# MainRTD.net
KiCad netlist of a schematic drawn in Altium Designer
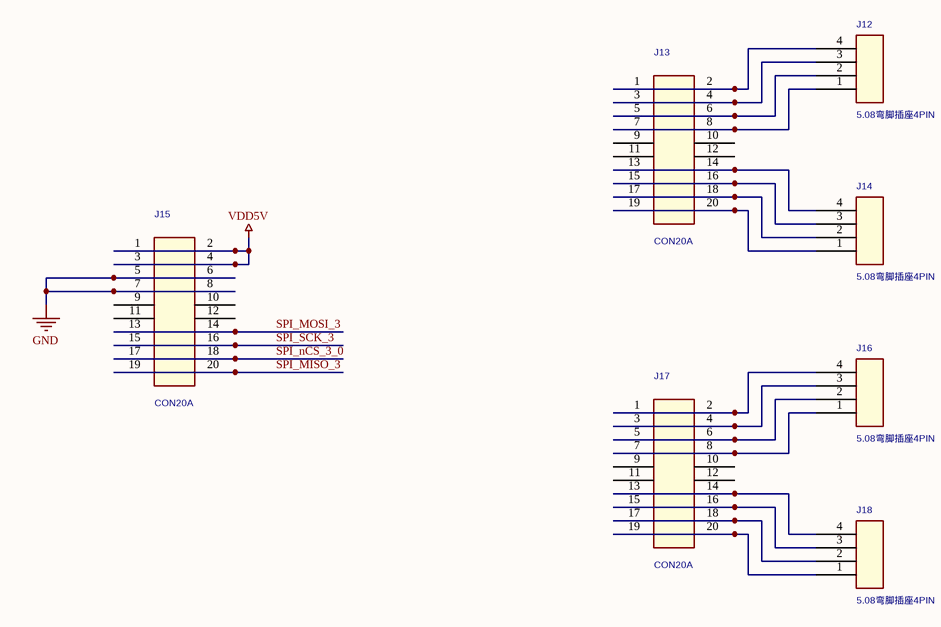
[diagram p0: MainRTD.SchDoc]

(export (version "E")
  (design (tool "Eeschema 10.0.6"))
  (components
    (comp (ref "J12") (value "5.08弯脚插座4PIN") (footprint "JIEKE_4PX508") (libsource (lib "*") (part "CON4")))
    (comp (ref "J13") (value "CON20A") (footprint "HDR2X10") (libsource (lib "*") (part "CON20A")))
    (comp (ref "J14") (value "5.08弯脚插座4PIN") (footprint "JIEKE_4PX508") (libsource (lib "*") (part "CON4")))
    (comp (ref "J15") (value "CON20A") (footprint "HDR2X10") (libsource (lib "*") (part "CON20A")))
    (comp (ref "J16") (value "5.08弯脚插座4PIN") (footprint "JIEKE_4PX508") (libsource (lib "*") (part "CON4")))
    (comp (ref "J17") (value "CON20A") (footprint "HDR2X10") (libsource (lib "*") (part "CON20A")))
    (comp (ref "J18") (value "5.08弯脚插座4PIN") (footprint "JIEKE_4PX508") (libsource (lib "*") (part "CON4")))
  )
  (nets
    (net (code "1") (name "/SPI_MISO_3") (class "Default")
      (node (ref "J15") (pin "19") (pinfunction "19_19") (pintype "passive"))
      (node (ref "J15") (pin "20") (pinfunction "20_20") (pintype "passive"))
    )
    (net (code "2") (name "/SPI_MOSI_3") (class "Default")
      (node (ref "J15") (pin "13") (pinfunction "13_13") (pintype "passive"))
      (node (ref "J15") (pin "14") (pinfunction "14_14") (pintype "passive"))
    )
    (net (code "3") (name "/SPI_SCK_3") (class "Default")
      (node (ref "J15") (pin "15") (pinfunction "15_15") (pintype "passive"))
      (node (ref "J15") (pin "16") (pinfunction "16_16") (pintype "passive"))
    )
    (net (code "4") (name "/SPI_nCS_3_0") (class "Default")
      (node (ref "J15") (pin "17") (pinfunction "17_17") (pintype "passive"))
      (node (ref "J15") (pin "18") (pinfunction "18_18") (pintype "passive"))
    )
    (net (code "5") (name "GND") (class "Default")
      (node (ref "J15") (pin "5") (pinfunction "5_5") (pintype "passive"))
      (node (ref "J15") (pin "6") (pinfunction "6_6") (pintype "passive"))
      (node (ref "J15") (pin "7") (pinfunction "7_7") (pintype "passive"))
      (node (ref "J15") (pin "8") (pinfunction "8_8") (pintype "passive"))
    )
    (net (code "6") (name "Net-(J12-Pad1)") (class "Default")
      (node (ref "J12") (pin "1") (pinfunction "1_1") (pintype "passive"))
      (node (ref "J13") (pin "7") (pinfunction "7_7") (pintype "passive"))
      (node (ref "J13") (pin "8") (pinfunction "8_8") (pintype "passive"))
    )
    (net (code "7") (name "Net-(J12-Pad2)") (class "Default")
      (node (ref "J12") (pin "2") (pinfunction "2_2") (pintype "passive"))
      (node (ref "J13") (pin "5") (pinfunction "5_5") (pintype "passive"))
      (node (ref "J13") (pin "6") (pinfunction "6_6") (pintype "passive"))
    )
    (net (code "8") (name "Net-(J12-Pad3)") (class "Default")
      (node (ref "J12") (pin "3") (pinfunction "3_3") (pintype "passive"))
      (node (ref "J13") (pin "3") (pinfunction "3_3") (pintype "passive"))
      (node (ref "J13") (pin "4") (pinfunction "4_4") (pintype "passive"))
    )
    (net (code "9") (name "Net-(J12-Pad4)") (class "Default")
      (node (ref "J12") (pin "4") (pinfunction "4_4") (pintype "passive"))
      (node (ref "J13") (pin "1") (pinfunction "1_1") (pintype "passive"))
      (node (ref "J13") (pin "2") (pinfunction "2_2") (pintype "passive"))
    )
    (net (code "10") (name "Net-(J13-Pad13)") (class "Default")
      (node (ref "J13") (pin "13") (pinfunction "13_13") (pintype "passive"))
      (node (ref "J13") (pin "14") (pinfunction "14_14") (pintype "passive"))
      (node (ref "J14") (pin "4") (pinfunction "4_4") (pintype "passive"))
    )
    (net (code "11") (name "Net-(J13-Pad15)") (class "Default")
      (node (ref "J13") (pin "15") (pinfunction "15_15") (pintype "passive"))
      (node (ref "J13") (pin "16") (pinfunction "16_16") (pintype "passive"))
      (node (ref "J14") (pin "3") (pinfunction "3_3") (pintype "passive"))
    )
    (net (code "12") (name "Net-(J13-Pad17)") (class "Default")
      (node (ref "J13") (pin "17") (pinfunction "17_17") (pintype "passive"))
      (node (ref "J13") (pin "18") (pinfunction "18_18") (pintype "passive"))
      (node (ref "J14") (pin "2") (pinfunction "2_2") (pintype "passive"))
    )
    (net (code "13") (name "Net-(J13-Pad19)") (class "Default")
      (node (ref "J13") (pin "19") (pinfunction "19_19") (pintype "passive"))
      (node (ref "J13") (pin "20") (pinfunction "20_20") (pintype "passive"))
      (node (ref "J14") (pin "1") (pinfunction "1_1") (pintype "passive"))
    )
    (net (code "14") (name "Net-(J16-Pad1)") (class "Default")
      (node (ref "J16") (pin "1") (pinfunction "1_1") (pintype "passive"))
      (node (ref "J17") (pin "7") (pinfunction "7_7") (pintype "passive"))
      (node (ref "J17") (pin "8") (pinfunction "8_8") (pintype "passive"))
    )
    (net (code "15") (name "Net-(J16-Pad2)") (class "Default")
      (node (ref "J16") (pin "2") (pinfunction "2_2") (pintype "passive"))
      (node (ref "J17") (pin "5") (pinfunction "5_5") (pintype "passive"))
      (node (ref "J17") (pin "6") (pinfunction "6_6") (pintype "passive"))
    )
    (net (code "16") (name "Net-(J16-Pad3)") (class "Default")
      (node (ref "J16") (pin "3") (pinfunction "3_3") (pintype "passive"))
      (node (ref "J17") (pin "3") (pinfunction "3_3") (pintype "passive"))
      (node (ref "J17") (pin "4") (pinfunction "4_4") (pintype "passive"))
    )
    (net (code "17") (name "Net-(J16-Pad4)") (class "Default")
      (node (ref "J16") (pin "4") (pinfunction "4_4") (pintype "passive"))
      (node (ref "J17") (pin "1") (pinfunction "1_1") (pintype "passive"))
      (node (ref "J17") (pin "2") (pinfunction "2_2") (pintype "passive"))
    )
    (net (code "18") (name "Net-(J17-Pad13)") (class "Default")
      (node (ref "J17") (pin "13") (pinfunction "13_13") (pintype "passive"))
      (node (ref "J17") (pin "14") (pinfunction "14_14") (pintype "passive"))
      (node (ref "J18") (pin "4") (pinfunction "4_4") (pintype "passive"))
    )
    (net (code "19") (name "Net-(J17-Pad15)") (class "Default")
      (node (ref "J17") (pin "15") (pinfunction "15_15") (pintype "passive"))
      (node (ref "J17") (pin "16") (pinfunction "16_16") (pintype "passive"))
      (node (ref "J18") (pin "3") (pinfunction "3_3") (pintype "passive"))
    )
    (net (code "20") (name "Net-(J17-Pad17)") (class "Default")
      (node (ref "J17") (pin "17") (pinfunction "17_17") (pintype "passive"))
      (node (ref "J17") (pin "18") (pinfunction "18_18") (pintype "passive"))
      (node (ref "J18") (pin "2") (pinfunction "2_2") (pintype "passive"))
    )
    (net (code "21") (name "Net-(J17-Pad19)") (class "Default")
      (node (ref "J17") (pin "19") (pinfunction "19_19") (pintype "passive"))
      (node (ref "J17") (pin "20") (pinfunction "20_20") (pintype "passive"))
      (node (ref "J18") (pin "1") (pinfunction "1_1") (pintype "passive"))
    )
    (net (code "22") (name "VDD5V") (class "Default")
      (node (ref "J15") (pin "1") (pinfunction "1_1") (pintype "passive"))
      (node (ref "J15") (pin "2") (pinfunction "2_2") (pintype "passive"))
      (node (ref "J15") (pin "3") (pinfunction "3_3") (pintype "passive"))
      (node (ref "J15") (pin "4") (pinfunction "4_4") (pintype "passive"))
    )
    (net (code "23") (name "unconnected-(J13-Pad9)") (class "Default")
      (node (ref "J13") (pin "9") (pinfunction "9_9") (pintype "passive"))
    )
    (net (code "24") (name "unconnected-(J13-Pad10)") (class "Default")
      (node (ref "J13") (pin "10") (pinfunction "10_10") (pintype "passive"))
    )
    (net (code "25") (name "unconnected-(J13-Pad11)") (class "Default")
      (node (ref "J13") (pin "11") (pinfunction "11_11") (pintype "passive"))
    )
    (net (code "26") (name "unconnected-(J13-Pad12)") (class "Default")
      (node (ref "J13") (pin "12") (pinfunction "12_12") (pintype "passive"))
    )
    (net (code "27") (name "unconnected-(J15-Pad9)") (class "Default")
      (node (ref "J15") (pin "9") (pinfunction "9_9") (pintype "passive"))
    )
    (net (code "28") (name "unconnected-(J15-Pad10)") (class "Default")
      (node (ref "J15") (pin "10") (pinfunction "10_10") (pintype "passive"))
    )
    (net (code "29") (name "unconnected-(J15-Pad11)") (class "Default")
      (node (ref "J15") (pin "11") (pinfunction "11_11") (pintype "passive"))
    )
    (net (code "30") (name "unconnected-(J15-Pad12)") (class "Default")
      (node (ref "J15") (pin "12") (pinfunction "12_12") (pintype "passive"))
    )
    (net (code "31") (name "unconnected-(J17-Pad9)") (class "Default")
      (node (ref "J17") (pin "9") (pinfunction "9_9") (pintype "passive"))
    )
    (net (code "32") (name "unconnected-(J17-Pad10)") (class "Default")
      (node (ref "J17") (pin "10") (pinfunction "10_10") (pintype "passive"))
    )
    (net (code "33") (name "unconnected-(J17-Pad11)") (class "Default")
      (node (ref "J17") (pin "11") (pinfunction "11_11") (pintype "passive"))
    )
    (net (code "34") (name "unconnected-(J17-Pad12)") (class "Default")
      (node (ref "J17") (pin "12") (pinfunction "12_12") (pintype "passive"))
    )
  )
)
